# P27_v3.net
KiCad netlist of a schematic drawn in EAGLE
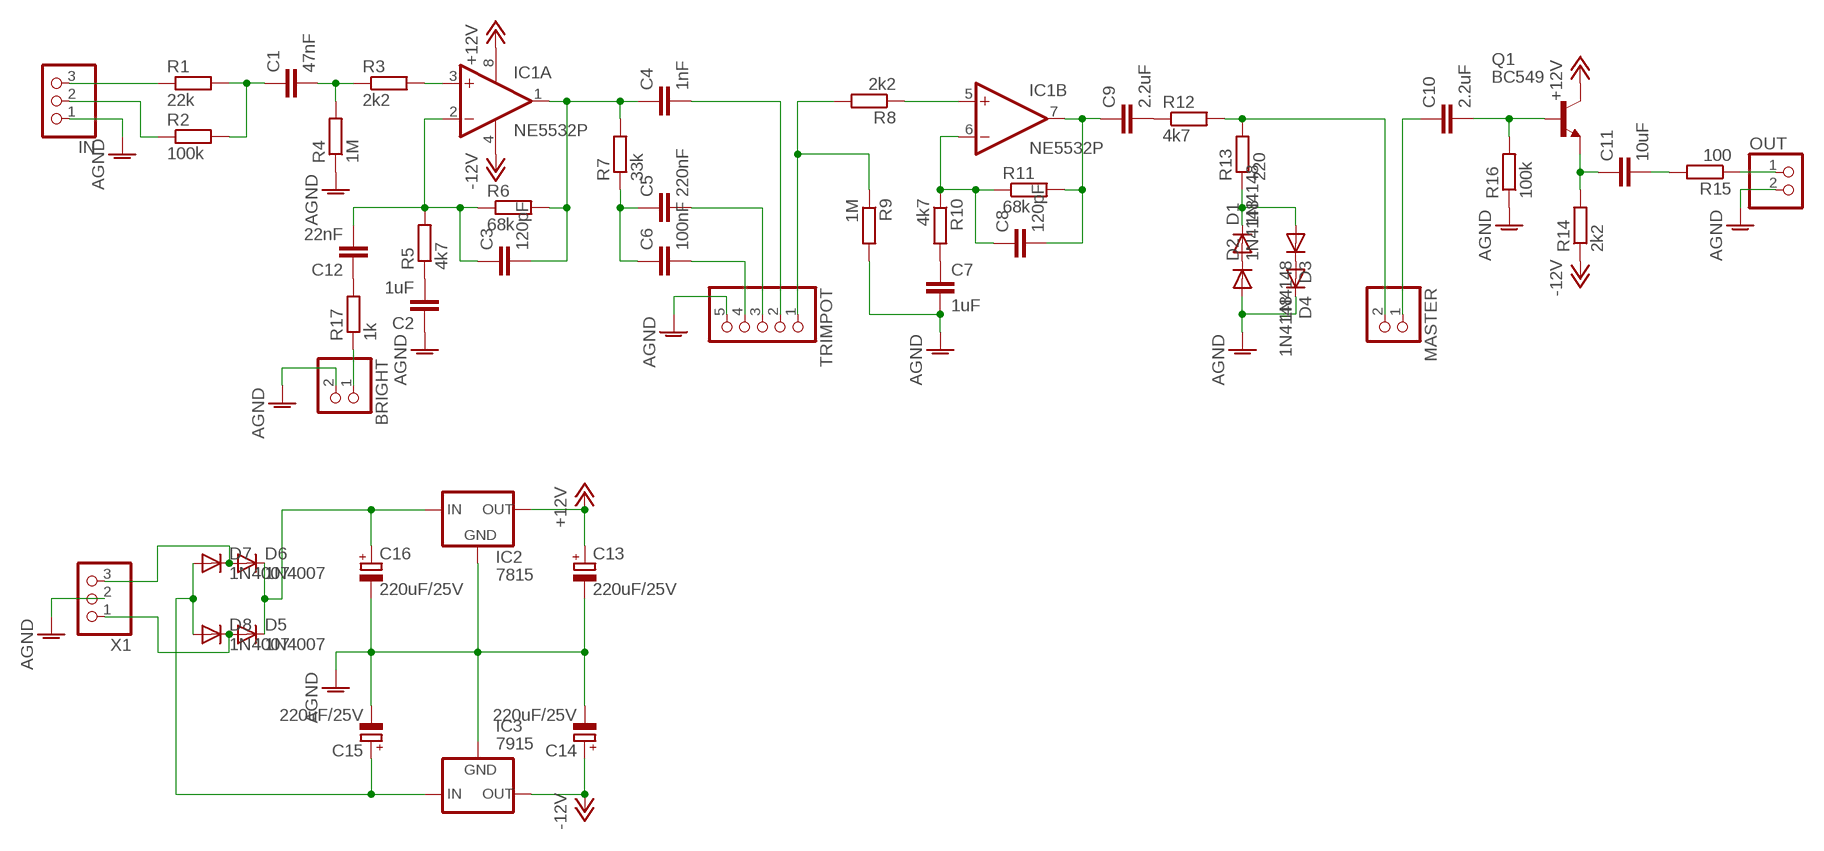
[diagram p0: schematic, sheet 1]

(export (version "E")
  (design (tool "Eeschema 10.0.6"))
  (components
    (comp (ref "BRIGHT")
      (value "PINHD-1X2")
      (footprint "eagle-import:1X02")
      (libsource (lib "eagle-import") (part "PINHD-1X2"))
    )
    (comp (ref "C1")
      (value "47nF")
      (footprint "eagle-import:C050-025X075")
      (libsource (lib "eagle-import") (part "C-EU050-025X075"))
    )
    (comp (ref "C2")
      (value "1uF")
      (footprint "eagle-import:C050-025X075")
      (libsource (lib "eagle-import") (part "C-EU050-025X075"))
    )
    (comp (ref "C3")
      (value "120pF")
      (footprint "eagle-import:C050-025X075")
      (libsource (lib "eagle-import") (part "C-EU050-025X075"))
    )
    (comp (ref "C4")
      (value "1nF")
      (footprint "eagle-import:C050-025X075")
      (libsource (lib "eagle-import") (part "C-EU050-025X075"))
    )
    (comp (ref "C5")
      (value "220nF")
      (footprint "eagle-import:C050-025X075")
      (libsource (lib "eagle-import") (part "C-EU050-025X075"))
    )
    (comp (ref "C6")
      (value "100nF")
      (footprint "eagle-import:C050-025X075")
      (libsource (lib "eagle-import") (part "C-EU050-025X075"))
    )
    (comp (ref "C7")
      (value "1uF")
      (footprint "eagle-import:C050-025X075")
      (libsource (lib "eagle-import") (part "C-EU050-025X075"))
    )
    (comp (ref "C8")
      (value "120pF")
      (footprint "eagle-import:C050-025X075")
      (libsource (lib "eagle-import") (part "C-EU050-025X075"))
    )
    (comp (ref "C9")
      (value "2.2uF")
      (footprint "eagle-import:C050-025X075")
      (libsource (lib "eagle-import") (part "C-EU050-025X075"))
    )
    (comp (ref "C10")
      (value "2.2uF")
      (footprint "eagle-import:C050-025X075")
      (libsource (lib "eagle-import") (part "C-EU050-025X075"))
    )
    (comp (ref "C11")
      (value "10uF")
      (footprint "eagle-import:C050-025X075")
      (libsource (lib "eagle-import") (part "C-EU050-025X075"))
    )
    (comp (ref "C12")
      (value "22nF")
      (footprint "eagle-import:C050-025X075")
      (libsource (lib "eagle-import") (part "C-EU050-025X075"))
    )
    (comp (ref "C13")
      (value "220uF/25V")
      (footprint "eagle-import:E2,5-6")
      (libsource (lib "eagle-import") (part "CPOL-EUE2.5-6"))
    )
    (comp (ref "C14")
      (value "220uF/25V")
      (footprint "eagle-import:E2,5-6")
      (libsource (lib "eagle-import") (part "CPOL-EUE2.5-6"))
    )
    (comp (ref "C15")
      (value "220uF/25V")
      (footprint "eagle-import:E2,5-6")
      (libsource (lib "eagle-import") (part "CPOL-EUE2.5-6"))
    )
    (comp (ref "C16")
      (value "220uF/25V")
      (footprint "eagle-import:E2,5-6")
      (libsource (lib "eagle-import") (part "CPOL-EUE2.5-6"))
    )
    (comp (ref "D1")
      (value "1N4148")
      (footprint "eagle-import:DO41-7")
      (libsource (lib "eagle-import") (part "1N4004D"))
    )
    (comp (ref "D2")
      (value "1N4148")
      (footprint "eagle-import:DO41-7")
      (libsource (lib "eagle-import") (part "1N4004D"))
    )
    (comp (ref "D3")
      (value "1N4148")
      (footprint "eagle-import:DO41-7")
      (libsource (lib "eagle-import") (part "1N4004D"))
    )
    (comp (ref "D4")
      (value "1N4148")
      (footprint "eagle-import:DO41-7")
      (libsource (lib "eagle-import") (part "1N4004D"))
    )
    (comp (ref "D5")
      (value "1N4007")
      (footprint "eagle-import:DO41-7")
      (libsource (lib "eagle-import") (part "1N4004D"))
    )
    (comp (ref "D6")
      (value "1N4007")
      (footprint "eagle-import:DO41-7")
      (libsource (lib "eagle-import") (part "1N4004D"))
    )
    (comp (ref "D7")
      (value "1N4007")
      (footprint "eagle-import:DO41-7")
      (libsource (lib "eagle-import") (part "1N4004D"))
    )
    (comp (ref "D8")
      (value "1N4007")
      (footprint "eagle-import:DO41-7")
      (libsource (lib "eagle-import") (part "1N4004D"))
    )
    (comp (ref "IC1")
      (value "NE5532P")
      (footprint "eagle-import:DIL08")
      (libsource (lib "eagle-import") (part "NE5532P"))
    )
    (comp (ref "IC2")
      (value "7815")
      (footprint "eagle-import:78XXS")
      (libsource (lib "eagle-import") (part "78XXTO-220"))
    )
    (comp (ref "IC3")
      (value "7915")
      (footprint "eagle-import:79XXS")
      (libsource (lib "eagle-import") (part "79XXTO-220"))
    )
    (comp (ref "IN")
      (value "PINHD-1X3180")
      (footprint "eagle-import:1X03")
      (libsource (lib "eagle-import") (part "PINHD-1X3180"))
    )
    (comp (ref "MASTER")
      (value "PINHD-1X2")
      (footprint "eagle-import:1X02")
      (libsource (lib "eagle-import") (part "PINHD-1X2"))
    )
    (comp (ref "OUT")
      (value "PINHD-1X2")
      (footprint "eagle-import:1X02")
      (libsource (lib "eagle-import") (part "PINHD-1X2"))
    )
    (comp (ref "Q1")
      (value "BC549")
      (footprint "eagle-import:TO92")
      (libsource (lib "eagle-import") (part "BC337"))
    )
    (comp (ref "R1")
      (value "22k")
      (footprint "eagle-import:0207_7")
      (libsource (lib "eagle-import") (part "R-EU_0207/7"))
    )
    (comp (ref "R2")
      (value "100k")
      (footprint "eagle-import:0207_7")
      (libsource (lib "eagle-import") (part "R-EU_0207/7"))
    )
    (comp (ref "R3")
      (value "2k2")
      (footprint "eagle-import:0207_7")
      (libsource (lib "eagle-import") (part "R-EU_0207/7"))
    )
    (comp (ref "R4")
      (value "1M")
      (footprint "eagle-import:0207_7")
      (libsource (lib "eagle-import") (part "R-EU_0207/7"))
    )
    (comp (ref "R5")
      (value "4k7")
      (footprint "eagle-import:0207_7")
      (libsource (lib "eagle-import") (part "R-EU_0207/7"))
    )
    (comp (ref "R6")
      (value "68k")
      (footprint "eagle-import:0207_7")
      (libsource (lib "eagle-import") (part "R-EU_0207/7"))
    )
    (comp (ref "R7")
      (value "33k")
      (footprint "eagle-import:0207_7")
      (libsource (lib "eagle-import") (part "R-EU_0207/7"))
    )
    (comp (ref "R8")
      (value "2k2")
      (footprint "eagle-import:0207_7")
      (libsource (lib "eagle-import") (part "R-EU_0207/7"))
    )
    (comp (ref "R9")
      (value "1M")
      (footprint "eagle-import:0207_7")
      (libsource (lib "eagle-import") (part "R-EU_0207/7"))
    )
    (comp (ref "R10")
      (value "4k7")
      (footprint "eagle-import:0207_7")
      (libsource (lib "eagle-import") (part "R-EU_0207/7"))
    )
    (comp (ref "R11")
      (value "68k")
      (footprint "eagle-import:0207_7")
      (libsource (lib "eagle-import") (part "R-EU_0207/7"))
    )
    (comp (ref "R12")
      (value "4k7")
      (footprint "eagle-import:0207_7")
      (libsource (lib "eagle-import") (part "R-EU_0207/7"))
    )
    (comp (ref "R13")
      (value "220")
      (footprint "eagle-import:0207_7")
      (libsource (lib "eagle-import") (part "R-EU_0207/7"))
    )
    (comp (ref "R14")
      (value "2k2")
      (footprint "eagle-import:0207_7")
      (libsource (lib "eagle-import") (part "R-EU_0207/7"))
    )
    (comp (ref "R15")
      (value "100")
      (footprint "eagle-import:0207_7")
      (libsource (lib "eagle-import") (part "R-EU_0207/7"))
    )
    (comp (ref "R16")
      (value "100k")
      (footprint "eagle-import:0207_7")
      (libsource (lib "eagle-import") (part "R-EU_0207/7"))
    )
    (comp (ref "R17")
      (value "1k")
      (footprint "eagle-import:0207_7")
      (libsource (lib "eagle-import") (part "R-EU_0207/7"))
    )
    (comp (ref "TRIMPOT")
      (value "PINHD-1X5")
      (footprint "eagle-import:1X05")
      (libsource (lib "eagle-import") (part "PINHD-1X5"))
    )
    (comp (ref "X1")
      (value "W237-103")
      (footprint "eagle-import:W237-103")
      (libsource (lib "eagle-import") (part "W237-103"))
    )
  )
  (nets
    (net (code "1") (name "+12V") (class "Default")
      (node (ref "C13") (pin "+") (pinfunction "+_+") (pintype "passive"))
      (node (ref "IC1") (pin "8") (pinfunction "V+_8") (pintype "power_in"))
      (node (ref "IC2") (pin "OUT") (pinfunction "OUT_OUT") (pintype "passive"))
      (node (ref "Q1") (pin "3") (pinfunction "C_3") (pintype "passive"))
    )
    (net (code "2") (name "-12V") (class "Default")
      (node (ref "C14") (pin "+") (pinfunction "+_+") (pintype "passive"))
      (node (ref "IC1") (pin "4") (pinfunction "V-_4") (pintype "power_in"))
      (node (ref "IC3") (pin "OUT") (pinfunction "OUT_OUT") (pintype "passive"))
      (node (ref "R14") (pin "1") (pinfunction "1_1") (pintype "passive"))
    )
    (net (code "3") (name "AGND") (class "Default")
      (node (ref "BRIGHT") (pin "2") (pinfunction "2_2") (pintype "passive"))
      (node (ref "C13") (pin "-") (pinfunction "-_-") (pintype "passive"))
      (node (ref "C14") (pin "-") (pinfunction "-_-") (pintype "passive"))
      (node (ref "C15") (pin "-") (pinfunction "-_-") (pintype "passive"))
      (node (ref "C16") (pin "-") (pinfunction "-_-") (pintype "passive"))
      (node (ref "C2") (pin "1") (pinfunction "1_1") (pintype "passive"))
      (node (ref "C7") (pin "2") (pinfunction "2_2") (pintype "passive"))
      (node (ref "D2") (pin "A") (pinfunction "A_A") (pintype "passive"))
      (node (ref "D4") (pin "C") (pinfunction "C_C") (pintype "passive"))
      (node (ref "IC2") (pin "GND") (pinfunction "GND_GND") (pintype "input"))
      (node (ref "IC3") (pin "GND") (pinfunction "GND_GND") (pintype "input"))
      (node (ref "IN") (pin "1") (pinfunction "1_1") (pintype "passive"))
      (node (ref "OUT") (pin "2") (pinfunction "2_2") (pintype "passive"))
      (node (ref "R16") (pin "1") (pinfunction "1_1") (pintype "passive"))
      (node (ref "R4") (pin "1") (pinfunction "1_1") (pintype "passive"))
      (node (ref "R9") (pin "2") (pinfunction "2_2") (pintype "passive"))
      (node (ref "TRIMPOT") (pin "5") (pinfunction "5_5") (pintype "passive"))
      (node (ref "X1") (pin "2") (pinfunction "2_2") (pintype "passive"))
    )
    (net (code "4") (name "Net-(BRIGHT-Pad1)") (class "Default")
      (node (ref "BRIGHT") (pin "1") (pinfunction "1_1") (pintype "passive"))
      (node (ref "R17") (pin "1") (pinfunction "1_1") (pintype "passive"))
    )
    (net (code "5") (name "Net-(C1-Pad1)") (class "Default")
      (node (ref "C1") (pin "1") (pinfunction "1_1") (pintype "passive"))
      (node (ref "R1") (pin "2") (pinfunction "2_2") (pintype "passive"))
      (node (ref "R2") (pin "2") (pinfunction "2_2") (pintype "passive"))
    )
    (net (code "6") (name "Net-(C1-Pad2)") (class "Default")
      (node (ref "C1") (pin "2") (pinfunction "2_2") (pintype "passive"))
      (node (ref "R3") (pin "1") (pinfunction "1_1") (pintype "passive"))
      (node (ref "R4") (pin "2") (pinfunction "2_2") (pintype "passive"))
    )
    (net (code "7") (name "Net-(C2-Pad2)") (class "Default")
      (node (ref "C2") (pin "2") (pinfunction "2_2") (pintype "passive"))
      (node (ref "R5") (pin "1") (pinfunction "1_1") (pintype "passive"))
    )
    (net (code "8") (name "Net-(C4-Pad2)") (class "Default")
      (node (ref "C4") (pin "2") (pinfunction "2_2") (pintype "passive"))
      (node (ref "TRIMPOT") (pin "2") (pinfunction "2_2") (pintype "passive"))
    )
    (net (code "9") (name "Net-(C5-Pad1)") (class "Default")
      (node (ref "C5") (pin "1") (pinfunction "1_1") (pintype "passive"))
      (node (ref "C6") (pin "1") (pinfunction "1_1") (pintype "passive"))
      (node (ref "R7") (pin "1") (pinfunction "1_1") (pintype "passive"))
    )
    (net (code "10") (name "Net-(C5-Pad2)") (class "Default")
      (node (ref "C5") (pin "2") (pinfunction "2_2") (pintype "passive"))
      (node (ref "TRIMPOT") (pin "3") (pinfunction "3_3") (pintype "passive"))
    )
    (net (code "11") (name "Net-(C6-Pad2)") (class "Default")
      (node (ref "C6") (pin "2") (pinfunction "2_2") (pintype "passive"))
      (node (ref "TRIMPOT") (pin "4") (pinfunction "4_4") (pintype "passive"))
    )
    (net (code "12") (name "Net-(C7-Pad1)") (class "Default")
      (node (ref "C7") (pin "1") (pinfunction "1_1") (pintype "passive"))
      (node (ref "R10") (pin "2") (pinfunction "2_2") (pintype "passive"))
    )
    (net (code "13") (name "Net-(C9-Pad2)") (class "Default")
      (node (ref "C9") (pin "2") (pinfunction "2_2") (pintype "passive"))
      (node (ref "R12") (pin "1") (pinfunction "1_1") (pintype "passive"))
    )
    (net (code "14") (name "Net-(C10-Pad1)") (class "Default")
      (node (ref "C10") (pin "1") (pinfunction "1_1") (pintype "passive"))
      (node (ref "MASTER") (pin "1") (pinfunction "1_1") (pintype "passive"))
    )
    (net (code "15") (name "Net-(C11-Pad2)") (class "Default")
      (node (ref "C11") (pin "2") (pinfunction "2_2") (pintype "passive"))
      (node (ref "R15") (pin "2") (pinfunction "2_2") (pintype "passive"))
    )
    (net (code "16") (name "Net-(C12-Pad1)") (class "Default")
      (node (ref "C12") (pin "1") (pinfunction "1_1") (pintype "passive"))
      (node (ref "R17") (pin "2") (pinfunction "2_2") (pintype "passive"))
    )
    (net (code "17") (name "Net-(C15-Pad+)") (class "Default")
      (node (ref "C15") (pin "+") (pinfunction "+_+") (pintype "passive"))
      (node (ref "D7") (pin "A") (pinfunction "A_A") (pintype "passive"))
      (node (ref "D8") (pin "A") (pinfunction "A_A") (pintype "passive"))
      (node (ref "IC3") (pin "IN") (pinfunction "IN_IN") (pintype "input"))
    )
    (net (code "18") (name "Net-(C16-Pad+)") (class "Default")
      (node (ref "C16") (pin "+") (pinfunction "+_+") (pintype "passive"))
      (node (ref "D5") (pin "C") (pinfunction "C_C") (pintype "passive"))
      (node (ref "D6") (pin "C") (pinfunction "C_C") (pintype "passive"))
      (node (ref "IC2") (pin "IN") (pinfunction "IN_IN") (pintype "input"))
    )
    (net (code "19") (name "Net-(D1-PadA)") (class "Default")
      (node (ref "D1") (pin "A") (pinfunction "A_A") (pintype "passive"))
      (node (ref "D2") (pin "C") (pinfunction "C_C") (pintype "passive"))
    )
    (net (code "20") (name "Net-(D1-PadC)") (class "Default")
      (node (ref "D1") (pin "C") (pinfunction "C_C") (pintype "passive"))
      (node (ref "D3") (pin "A") (pinfunction "A_A") (pintype "passive"))
      (node (ref "R13") (pin "1") (pinfunction "1_1") (pintype "passive"))
    )
    (net (code "21") (name "Net-(D3-PadC)") (class "Default")
      (node (ref "D3") (pin "C") (pinfunction "C_C") (pintype "passive"))
      (node (ref "D4") (pin "A") (pinfunction "A_A") (pintype "passive"))
    )
    (net (code "22") (name "Net-(D5-PadA)") (class "Default")
      (node (ref "D5") (pin "A") (pinfunction "A_A") (pintype "passive"))
      (node (ref "D8") (pin "C") (pinfunction "C_C") (pintype "passive"))
      (node (ref "X1") (pin "1") (pinfunction "1_1") (pintype "passive"))
    )
    (net (code "23") (name "Net-(D6-PadA)") (class "Default")
      (node (ref "D6") (pin "A") (pinfunction "A_A") (pintype "passive"))
      (node (ref "D7") (pin "C") (pinfunction "C_C") (pintype "passive"))
      (node (ref "X1") (pin "3") (pinfunction "3_3") (pintype "passive"))
    )
    (net (code "24") (name "Net-(IC1A-+IN)") (class "Default")
      (node (ref "IC1") (pin "3") (pinfunction "+IN_3") (pintype "input"))
      (node (ref "R3") (pin "2") (pinfunction "2_2") (pintype "passive"))
    )
    (net (code "25") (name "Net-(IC1A--IN)") (class "Default")
      (node (ref "C12") (pin "2") (pinfunction "2_2") (pintype "passive"))
      (node (ref "C3") (pin "1") (pinfunction "1_1") (pintype "passive"))
      (node (ref "IC1") (pin "2") (pinfunction "-IN_2") (pintype "input"))
      (node (ref "R5") (pin "2") (pinfunction "2_2") (pintype "passive"))
      (node (ref "R6") (pin "1") (pinfunction "1_1") (pintype "passive"))
    )
    (net (code "26") (name "Net-(IC1A-OUT)") (class "Default")
      (node (ref "C3") (pin "2") (pinfunction "2_2") (pintype "passive"))
      (node (ref "C4") (pin "1") (pinfunction "1_1") (pintype "passive"))
      (node (ref "IC1") (pin "1") (pinfunction "OUT_1") (pintype "output"))
      (node (ref "R6") (pin "2") (pinfunction "2_2") (pintype "passive"))
      (node (ref "R7") (pin "2") (pinfunction "2_2") (pintype "passive"))
    )
    (net (code "27") (name "Net-(IC1B-+IN)") (class "Default")
      (node (ref "IC1") (pin "5") (pinfunction "+IN_5") (pintype "input"))
      (node (ref "R8") (pin "1") (pinfunction "1_1") (pintype "passive"))
    )
    (net (code "28") (name "Net-(IC1B--IN)") (class "Default")
      (node (ref "C8") (pin "1") (pinfunction "1_1") (pintype "passive"))
      (node (ref "IC1") (pin "6") (pinfunction "-IN_6") (pintype "input"))
      (node (ref "R10") (pin "1") (pinfunction "1_1") (pintype "passive"))
      (node (ref "R11") (pin "1") (pinfunction "1_1") (pintype "passive"))
    )
    (net (code "29") (name "Net-(IC1B-OUT)") (class "Default")
      (node (ref "C8") (pin "2") (pinfunction "2_2") (pintype "passive"))
      (node (ref "C9") (pin "1") (pinfunction "1_1") (pintype "passive"))
      (node (ref "IC1") (pin "7") (pinfunction "OUT_7") (pintype "output"))
      (node (ref "R11") (pin "2") (pinfunction "2_2") (pintype "passive"))
    )
    (net (code "30") (name "Net-(IN-Pad2)") (class "Default")
      (node (ref "IN") (pin "2") (pinfunction "2_2") (pintype "passive"))
      (node (ref "R2") (pin "1") (pinfunction "1_1") (pintype "passive"))
    )
    (net (code "31") (name "Net-(IN-Pad3)") (class "Default")
      (node (ref "IN") (pin "3") (pinfunction "3_3") (pintype "passive"))
      (node (ref "R1") (pin "1") (pinfunction "1_1") (pintype "passive"))
    )
    (net (code "32") (name "Net-(MASTER-Pad2)") (class "Default")
      (node (ref "MASTER") (pin "2") (pinfunction "2_2") (pintype "passive"))
      (node (ref "R12") (pin "2") (pinfunction "2_2") (pintype "passive"))
      (node (ref "R13") (pin "2") (pinfunction "2_2") (pintype "passive"))
    )
    (net (code "33") (name "Net-(OUT-Pad1)") (class "Default")
      (node (ref "OUT") (pin "1") (pinfunction "1_1") (pintype "passive"))
      (node (ref "R15") (pin "1") (pinfunction "1_1") (pintype "passive"))
    )
    (net (code "34") (name "Net-(Q1-B)") (class "Default")
      (node (ref "C10") (pin "2") (pinfunction "2_2") (pintype "passive"))
      (node (ref "Q1") (pin "2") (pinfunction "B_2") (pintype "passive"))
      (node (ref "R16") (pin "2") (pinfunction "2_2") (pintype "passive"))
    )
    (net (code "35") (name "Net-(Q1-E)") (class "Default")
      (node (ref "C11") (pin "1") (pinfunction "1_1") (pintype "passive"))
      (node (ref "Q1") (pin "1") (pinfunction "E_1") (pintype "passive"))
      (node (ref "R14") (pin "2") (pinfunction "2_2") (pintype "passive"))
    )
    (net (code "36") (name "Net-(R8-Pad2)") (class "Default")
      (node (ref "R8") (pin "2") (pinfunction "2_2") (pintype "passive"))
      (node (ref "R9") (pin "1") (pinfunction "1_1") (pintype "passive"))
      (node (ref "TRIMPOT") (pin "1") (pinfunction "1_1") (pintype "passive"))
    )
  )
)
